# Ampli-2020.net
KiCad netlist of a schematic drawn in EAGLE
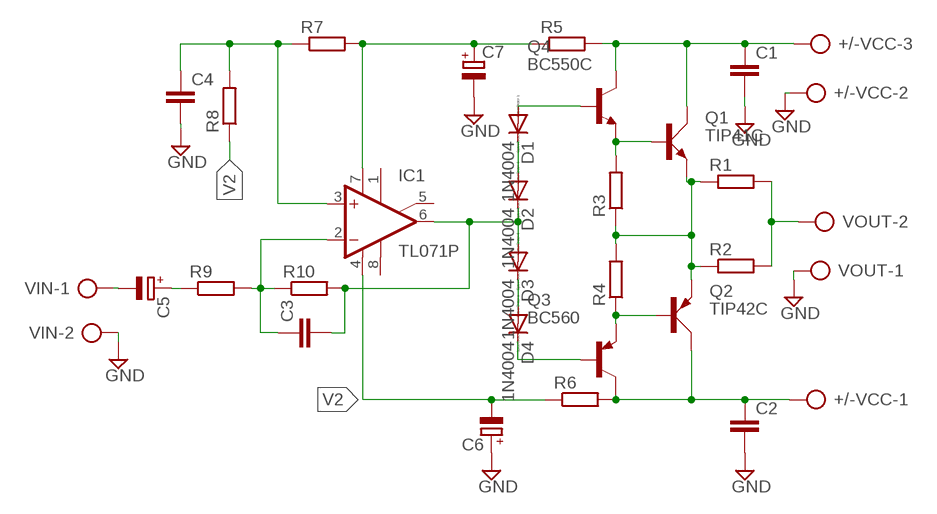
[diagram p0: schematic, sheet 1]

(export (version "E")
  (design (tool "Eeschema 10.0.6"))
  (components
    (comp (ref "+/-VCC")
      (value "AK500/3")
      (footprint "eagle-import:AK500_3")
      (libsource (lib "eagle-import") (part "AK500/3"))
    )
    (comp (ref "C1")
      (value "C-EU050-025X075")
      (footprint "eagle-import:C050-025X075")
      (libsource (lib "eagle-import") (part "C-EU050-025X075"))
    )
    (comp (ref "C2")
      (value "C-EU050-025X075")
      (footprint "eagle-import:C050-025X075")
      (libsource (lib "eagle-import") (part "C-EU050-025X075"))
    )
    (comp (ref "C3")
      (value "C-EU050-025X075")
      (footprint "eagle-import:C050-025X075")
      (libsource (lib "eagle-import") (part "C-EU050-025X075"))
    )
    (comp (ref "C4")
      (value "C-EU050-025X075")
      (footprint "eagle-import:C050-025X075")
      (libsource (lib "eagle-import") (part "C-EU050-025X075"))
    )
    (comp (ref "C5")
      (value "CPOL-EUE2.5-5")
      (footprint "eagle-import:E2,5-5")
      (libsource (lib "eagle-import") (part "CPOL-EUE2.5-5"))
    )
    (comp (ref "C6")
      (value "CPOL-EUE2.5-7")
      (footprint "eagle-import:E2,5-7")
      (libsource (lib "eagle-import") (part "CPOL-EUE2.5-7"))
    )
    (comp (ref "C7")
      (value "CPOL-EUE2.5-7")
      (footprint "eagle-import:E2,5-7")
      (libsource (lib "eagle-import") (part "CPOL-EUE2.5-7"))
    )
    (comp (ref "D1")
      (value "1N4004")
      (footprint "eagle-import:DO41-10")
      (libsource (lib "eagle-import") (part "1N4004"))
    )
    (comp (ref "D2")
      (value "1N4004")
      (footprint "eagle-import:DO41-10")
      (libsource (lib "eagle-import") (part "1N4004"))
    )
    (comp (ref "D3")
      (value "1N4004")
      (footprint "eagle-import:DO41-10")
      (libsource (lib "eagle-import") (part "1N4004"))
    )
    (comp (ref "D4")
      (value "1N4004")
      (footprint "eagle-import:DO41-10")
      (libsource (lib "eagle-import") (part "1N4004"))
    )
    (comp (ref "IC1")
      (value "TL071P")
      (footprint "eagle-import:DIL08")
      (libsource (lib "eagle-import") (part "TL071P"))
    )
    (comp (ref "Q1")
      (value "TIP41C")
      (footprint "eagle-import:TO220AV")
      (libsource (lib "eagle-import") (part "TIP41C"))
    )
    (comp (ref "Q2")
      (value "TIP42C")
      (footprint "eagle-import:TO220AV")
      (libsource (lib "eagle-import") (part "TIP42C"))
    )
    (comp (ref "Q3")
      (value "BC560")
      (footprint "eagle-import:TO92-EBC")
      (libsource (lib "eagle-import") (part "BC560"))
    )
    (comp (ref "Q4")
      (value "BC550C")
      (footprint "eagle-import:TO92-EBC")
      (libsource (lib "eagle-import") (part "BC550C"))
    )
    (comp (ref "R1")
      (value "R-EU_0617/17")
      (footprint "eagle-import:0617_17")
      (libsource (lib "eagle-import") (part "R-EU_0617/17"))
    )
    (comp (ref "R2")
      (value "R-EU_0617/17")
      (footprint "eagle-import:0617_17")
      (libsource (lib "eagle-import") (part "R-EU_0617/17"))
    )
    (comp (ref "R3")
      (value "R-EU_0207/7")
      (footprint "eagle-import:0207_7")
      (libsource (lib "eagle-import") (part "R-EU_0207/7"))
    )
    (comp (ref "R4")
      (value "R-EU_0207/7")
      (footprint "eagle-import:0207_7")
      (libsource (lib "eagle-import") (part "R-EU_0207/7"))
    )
    (comp (ref "R5")
      (value "R-EU_0207/7")
      (footprint "eagle-import:0207_7")
      (libsource (lib "eagle-import") (part "R-EU_0207/7"))
    )
    (comp (ref "R6")
      (value "R-EU_0207/7")
      (footprint "eagle-import:0207_7")
      (libsource (lib "eagle-import") (part "R-EU_0207/7"))
    )
    (comp (ref "R7")
      (value "R-EU_0207/7")
      (footprint "eagle-import:0207_7")
      (libsource (lib "eagle-import") (part "R-EU_0207/7"))
    )
    (comp (ref "R8")
      (value "R-EU_0207/7")
      (footprint "eagle-import:0207_7")
      (libsource (lib "eagle-import") (part "R-EU_0207/7"))
    )
    (comp (ref "R9")
      (value "R-EU_0207/7")
      (footprint "eagle-import:0207_7")
      (libsource (lib "eagle-import") (part "R-EU_0207/7"))
    )
    (comp (ref "R10")
      (value "R-EU_0207/7")
      (footprint "eagle-import:0207_7")
      (libsource (lib "eagle-import") (part "R-EU_0207/7"))
    )
    (comp (ref "VIN")
      (value "AK500/2")
      (footprint "eagle-import:AK500_2")
      (libsource (lib "eagle-import") (part "AK500/2"))
    )
    (comp (ref "VOUT")
      (value "AK500/2")
      (footprint "eagle-import:AK500_2")
      (libsource (lib "eagle-import") (part "AK500/2"))
    )
  )
  (nets
    (net (code "1") (name "GND") (class "Default")
      (node (ref "+/-VCC") (pin "2") (pinfunction "KL_2") (pintype "passive"))
      (node (ref "C1") (pin "2") (pinfunction "2_2") (pintype "passive"))
      (node (ref "C2") (pin "2") (pinfunction "2_2") (pintype "passive"))
      (node (ref "C4") (pin "2") (pinfunction "2_2") (pintype "passive"))
      (node (ref "C6") (pin "+") (pinfunction "+_+") (pintype "passive"))
      (node (ref "C7") (pin "-") (pinfunction "-_-") (pintype "passive"))
      (node (ref "VIN") (pin "2") (pinfunction "KL_2") (pintype "passive"))
      (node (ref "VOUT") (pin "1") (pinfunction "KL_1") (pintype "passive"))
    )
    (net (code "2") (name "Net-(+/-VCCA-KL)") (class "Default")
      (node (ref "+/-VCC") (pin "1") (pinfunction "KL_1") (pintype "passive"))
      (node (ref "C2") (pin "1") (pinfunction "1_1") (pintype "passive"))
      (node (ref "Q2") (pin "C") (pinfunction "C_C") (pintype "passive"))
      (node (ref "Q3") (pin "C") (pinfunction "C_C") (pintype "passive"))
      (node (ref "R6") (pin "2") (pinfunction "2_2") (pintype "passive"))
    )
    (net (code "3") (name "Net-(+/-VCCC-KL)") (class "Default")
      (node (ref "+/-VCC") (pin "3") (pinfunction "KL_3") (pintype "passive"))
      (node (ref "C1") (pin "1") (pinfunction "1_1") (pintype "passive"))
      (node (ref "Q1") (pin "C") (pinfunction "C_C") (pintype "passive"))
      (node (ref "Q4") (pin "C") (pinfunction "C_C") (pintype "passive"))
      (node (ref "R5") (pin "2") (pinfunction "2_2") (pintype "passive"))
    )
    (net (code "4") (name "Net-(C5-Pad+)") (class "Default")
      (node (ref "C5") (pin "+") (pinfunction "+_+") (pintype "passive"))
      (node (ref "R9") (pin "1") (pinfunction "1_1") (pintype "passive"))
    )
    (net (code "5") (name "Net-(D1-PadA)") (class "Default")
      (node (ref "D1") (pin "A") (pinfunction "A_A") (pintype "passive"))
      (node (ref "Q4") (pin "B") (pinfunction "B_B") (pintype "passive"))
    )
    (net (code "6") (name "Net-(D1-PadC)") (class "Default")
      (node (ref "D1") (pin "C") (pinfunction "C_C") (pintype "passive"))
      (node (ref "D2") (pin "A") (pinfunction "A_A") (pintype "passive"))
    )
    (net (code "7") (name "Net-(D3-PadC)") (class "Default")
      (node (ref "D3") (pin "C") (pinfunction "C_C") (pintype "passive"))
      (node (ref "D4") (pin "A") (pinfunction "A_A") (pintype "passive"))
    )
    (net (code "8") (name "Net-(D4-PadC)") (class "Default")
      (node (ref "D4") (pin "C") (pinfunction "C_C") (pintype "passive"))
      (node (ref "Q3") (pin "B") (pinfunction "B_B") (pintype "passive"))
    )
    (net (code "9") (name "Net-(IC1-+IN)") (class "Default")
      (node (ref "C4") (pin "1") (pinfunction "1_1") (pintype "passive"))
      (node (ref "IC1") (pin "3") (pinfunction "+IN_3") (pintype "input"))
      (node (ref "R7") (pin "1") (pinfunction "1_1") (pintype "passive"))
      (node (ref "R8") (pin "2") (pinfunction "2_2") (pintype "passive"))
    )
    (net (code "10") (name "Net-(IC1--IN)") (class "Default")
      (node (ref "C3") (pin "1") (pinfunction "1_1") (pintype "passive"))
      (node (ref "IC1") (pin "2") (pinfunction "-IN_2") (pintype "input"))
      (node (ref "R10") (pin "1") (pinfunction "1_1") (pintype "passive"))
      (node (ref "R9") (pin "2") (pinfunction "2_2") (pintype "passive"))
    )
    (net (code "11") (name "Net-(IC1-OUT)") (class "Default")
      (node (ref "C3") (pin "2") (pinfunction "2_2") (pintype "passive"))
      (node (ref "D2") (pin "C") (pinfunction "C_C") (pintype "passive"))
      (node (ref "D3") (pin "A") (pinfunction "A_A") (pintype "passive"))
      (node (ref "IC1") (pin "6") (pinfunction "OUT_6") (pintype "output"))
      (node (ref "R10") (pin "2") (pinfunction "2_2") (pintype "passive"))
    )
    (net (code "12") (name "Net-(IC1-V+)") (class "Default")
      (node (ref "C7") (pin "+") (pinfunction "+_+") (pintype "passive"))
      (node (ref "IC1") (pin "7") (pinfunction "V+_7") (pintype "power_in"))
      (node (ref "R5") (pin "1") (pinfunction "1_1") (pintype "passive"))
      (node (ref "R7") (pin "2") (pinfunction "2_2") (pintype "passive"))
    )
    (net (code "13") (name "Net-(Q1-PadB)") (class "Default")
      (node (ref "Q1") (pin "B") (pinfunction "B_B") (pintype "passive"))
      (node (ref "Q4") (pin "E") (pinfunction "E_E") (pintype "passive"))
      (node (ref "R3") (pin "2") (pinfunction "2_2") (pintype "passive"))
    )
    (net (code "14") (name "Net-(Q1-PadE)") (class "Default")
      (node (ref "Q1") (pin "E") (pinfunction "E_E") (pintype "passive"))
      (node (ref "Q2") (pin "E") (pinfunction "E_E") (pintype "passive"))
      (node (ref "R1") (pin "1") (pinfunction "1_1") (pintype "passive"))
      (node (ref "R2") (pin "1") (pinfunction "1_1") (pintype "passive"))
      (node (ref "R3") (pin "1") (pinfunction "1_1") (pintype "passive"))
      (node (ref "R4") (pin "2") (pinfunction "2_2") (pintype "passive"))
    )
    (net (code "15") (name "Net-(Q2-PadB)") (class "Default")
      (node (ref "Q2") (pin "B") (pinfunction "B_B") (pintype "passive"))
      (node (ref "Q3") (pin "E") (pinfunction "E_E") (pintype "passive"))
      (node (ref "R4") (pin "1") (pinfunction "1_1") (pintype "passive"))
    )
    (net (code "16") (name "Net-(VINA-KL)") (class "Default")
      (node (ref "C5") (pin "-") (pinfunction "-_-") (pintype "passive"))
      (node (ref "VIN") (pin "1") (pinfunction "KL_1") (pintype "passive"))
    )
    (net (code "17") (name "Net-(VOUTB-KL)") (class "Default")
      (node (ref "R1") (pin "2") (pinfunction "2_2") (pintype "passive"))
      (node (ref "R2") (pin "2") (pinfunction "2_2") (pintype "passive"))
      (node (ref "VOUT") (pin "2") (pinfunction "KL_2") (pintype "passive"))
    )
    (net (code "18") (name "V2") (class "Default")
      (node (ref "C6") (pin "-") (pinfunction "-_-") (pintype "passive"))
      (node (ref "IC1") (pin "4") (pinfunction "V-_4") (pintype "power_in"))
      (node (ref "R6") (pin "1") (pinfunction "1_1") (pintype "passive"))
      (node (ref "R8") (pin "1") (pinfunction "1_1") (pintype "passive"))
    )
    (net (code "19") (name "unconnected-(IC1-ON1-Pad1)") (class "Default")
      (node (ref "IC1") (pin "1") (pinfunction "ON1_1") (pintype "passive"))
    )
    (net (code "20") (name "unconnected-(IC1-ON2-Pad5)") (class "Default")
      (node (ref "IC1") (pin "5") (pinfunction "ON2_5") (pintype "passive"))
    )
    (net (code "21") (name "unconnected-(IC1-OPT-Pad8)") (class "Default")
      (node (ref "IC1") (pin "8") (pinfunction "OPT_8") (pintype "passive"))
    )
  )
)
